# Fluid_Flow_FE.net
KiCad netlist of a schematic drawn in Altium Designer
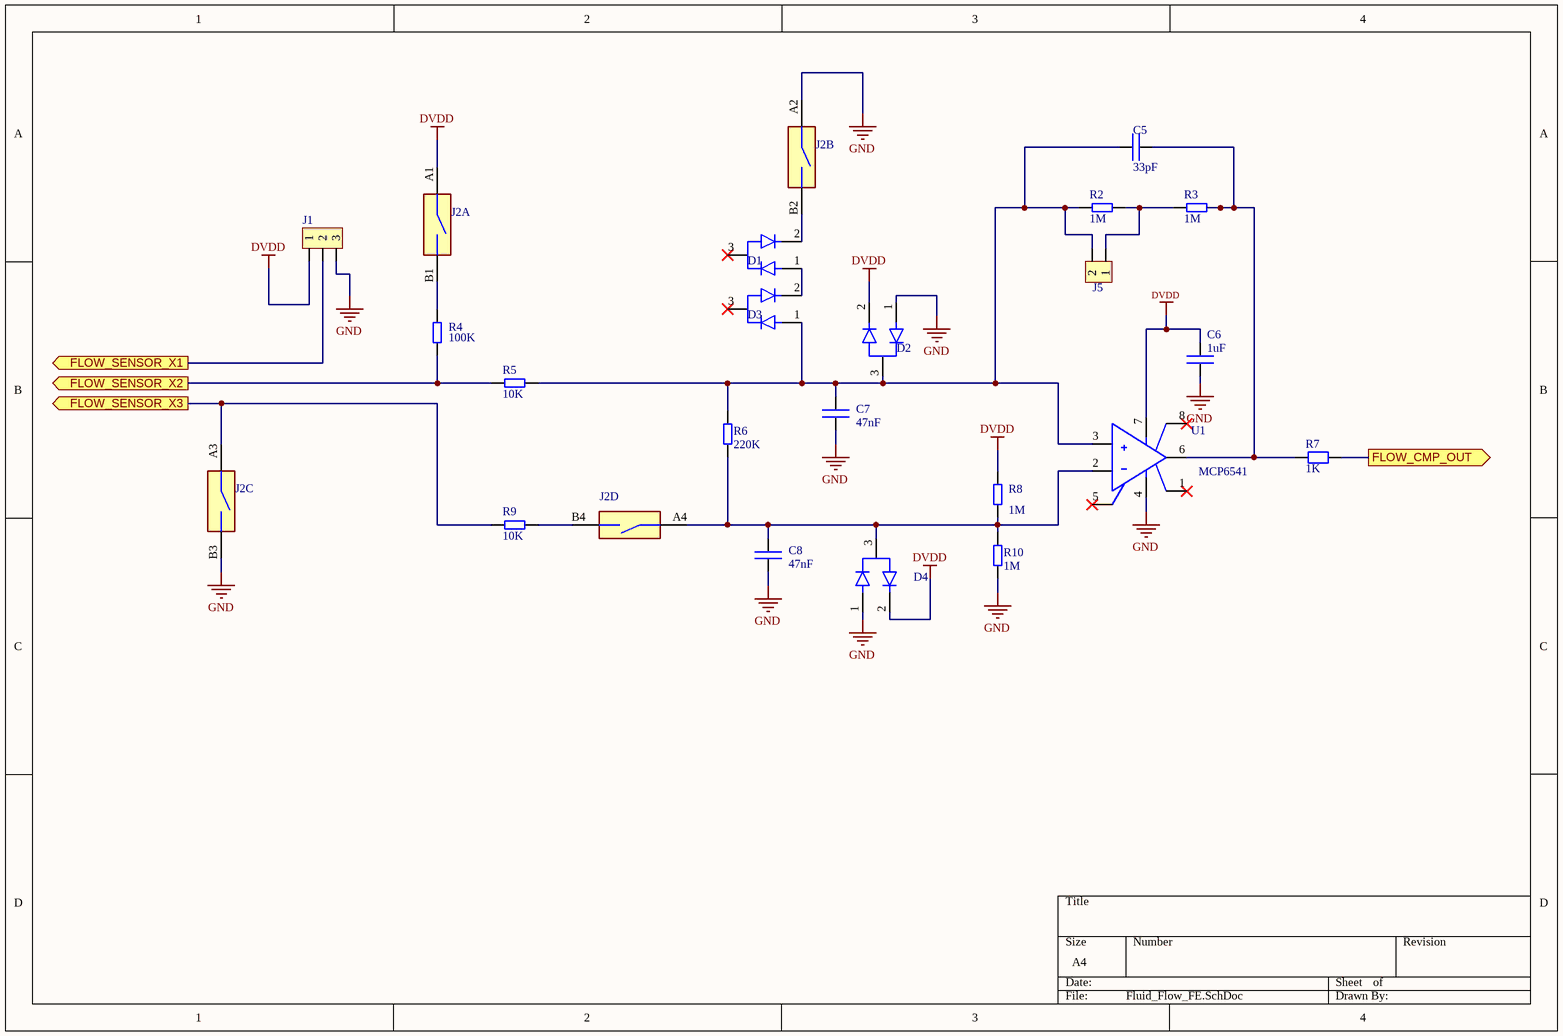
[diagram p0: Fluid_Flow_FE.SchDoc]

(export (version "E")
  (design (tool "Eeschema 10.0.6"))
  (components
    (comp (ref "C5")
      (value "33pF")
      (footprint "CAP_SM0603_YAGEOCC2_N")
      (description "CAP 33pF SM0603 NPO 50V YAGEO CC2")
      (fields
        (field (name "MANUFACTURER") "Yageo")
        (field (name "MANUFACTURER PART NUMBER") "CC0603JRNPO9BN330")
      )
      (libsource (lib "yageo") (part "CC0603JRNPO9BN330"))
    )
    (comp (ref "C6")
      (value "1uF")
      (footprint "CAP_SM0603_YAGEOCC2_N")
      (description "CAP 1uF SM0603 X7R 10V YAGEO CC2")
      (fields
        (field (name "MANUFACTURER") "Yageo")
        (field (name "MANUFACTURER PART NUMBER") "CC0603KRX7R6BB105")
      )
      (libsource (lib "yageo") (part "CC0603KRX7R6BB105"))
    )
    (comp (ref "C7")
      (value "47nF")
      (footprint "CAP_SM0603_YAGEOCC2_N")
      (description "CAP 47nF SM0603 X7R 16V YAGEO")
      (fields
        (field (name "MANUFACTURER") "Yageo")
        (field (name "MANUFACTURER PART NUMBER") "CC0603JRX7R7BB473")
      )
      (libsource (lib "yageo") (part "CC0603JRX7R7BB473"))
    )
    (comp (ref "C8")
      (value "47nF")
      (footprint "CAP_SM0603_YAGEOCC2_N")
      (description "CAP 47nF SM0603 X7R 16V YAGEO")
      (fields
        (field (name "MANUFACTURER") "Yageo")
        (field (name "MANUFACTURER PART NUMBER") "CC0603JRX7R7BB473")
      )
      (libsource (lib "yageo") (part "CC0603JRX7R7BB473"))
    )
    (comp (ref "D1")
      (value "BAV23S")
      (footprint "BAV23S")
      (description "DIODE ARRAY GP 250V 200MA SOT23")
      (fields (field (name "MANUFACTURER") "onsemi"))
      (libsource (lib "flowmeet") (part "BAV23S"))
    )
    (comp (ref "D2")
      (value "BAV23S")
      (footprint "BAV23S")
      (description "DIODE ARRAY GP 250V 200MA SOT23")
      (fields (field (name "MANUFACTURER") "onsemi"))
      (libsource (lib "flowmeet") (part "BAV23S"))
    )
    (comp (ref "D3")
      (value "BAV23S")
      (footprint "BAV23S")
      (description "DIODE ARRAY GP 250V 200MA SOT23")
      (fields (field (name "MANUFACTURER") "onsemi"))
      (libsource (lib "flowmeet") (part "BAV23S"))
    )
    (comp (ref "D4")
      (value "BAV23S")
      (footprint "BAV23S")
      (description "DIODE ARRAY GP 250V 200MA SOT23")
      (fields (field (name "MANUFACTURER") "onsemi"))
      (libsource (lib "flowmeet") (part "BAV23S"))
    )
    (comp (ref "J1")
      (value "54101-T0600LF-CUT-3")
      (footprint "HEADER PIN 1X3")
      (description "Pin header pitch 2.54 TH - cuttable 3 od 36 positions.")
      (fields
        (field (name "MANUFACTURER") "Amphenol ICC")
        (field (name "MANUFACTURER PART NUMBER") "54101-T0600LF")
      )
      (libsource (lib "flowmeet") (part "54101-T0600LF-CUT-3"))
    )
    (comp (ref "J2")
      (value "DSHP04TSGER_1")
      (footprint "DSHP04TSGER")
      (description "DIP Switches / SIP Switches 4pos 0.025A 24VDC 1/2 Pitch")
      (fields
        (field (name "MANUFACTURER") "Kangshen")
        (field (name "MANUFACTURER PART NUMBER") "DSHP04TSGER")
      )
      (libsource (lib "") (part "DSHP04TSGER_1_1"))
    )
    (comp (ref "J5")
      (value "54101-T0600LF-CUT-2")
      (footprint "HEADER PIN 1X2")
      (description "Pin header pitch 2.54 TH - cuttable 2 od 36 positions.")
      (fields
        (field (name "MANUFACTURER") "Amphenol ICC")
        (field (name "MANUFACTURER PART NUMBER") "54101-T0600LF")
      )
      (libsource (lib "flowmeet") (part "54101-T0600LF-CUT-2"))
    )
    (comp (ref "R2")
      (value "1M")
      (footprint "RES_SM0603_YAGEORC_N")
      (description "RES 1M SM0603 YAGEO RC_L")
      (fields
        (field (name "MANUFACTURER") "Yageo")
        (field (name "MANUFACTURER PART NUMBER") "RC0603FR-071ML")
      )
      (libsource (lib "") (part "RC0603FR-071ML_1"))
    )
    (comp (ref "R3")
      (value "1M")
      (footprint "RES_SM0603_YAGEORC_N")
      (description "RES 1M SM0603 YAGEO RC_L")
      (fields
        (field (name "MANUFACTURER") "Yageo")
        (field (name "MANUFACTURER PART NUMBER") "RC0603FR-071ML")
      )
      (libsource (lib "") (part "RC0603FR-071ML_1"))
    )
    (comp (ref "R4")
      (value "100K")
      (footprint "RES_SM0603_YAGEORC_N")
      (description "RES 100K SM0603 YAGEO RC_L")
      (fields
        (field (name "MANUFACTURER") "Yageo")
        (field (name "MANUFACTURER PART NUMBER") "RC0603FR-13100KL")
      )
      (libsource (lib "yageo") (part "RC0603FR-13100KL"))
    )
    (comp (ref "R5")
      (value "10K")
      (footprint "RES_SM0603_YAGEORC_N")
      (description "RES 10K SM0603 YAGEO RC_L")
      (fields
        (field (name "MANUFACTURER") "Yageo")
        (field (name "MANUFACTURER PART NUMBER") "RC0603FR-0710KL")
      )
      (libsource (lib "yageo") (part "RC0603FR-0710KL"))
    )
    (comp (ref "R6")
      (value "220K")
      (footprint "RES_SM0603_YAGEORC_N")
      (description "RES 220K SM0603 YAGEO RC_L")
      (fields
        (field (name "MANUFACTURER") "Yageo")
        (field (name "MANUFACTURER PART NUMBER") "RC0603FR-07220KL")
      )
      (libsource (lib "yageo") (part "RC0603FR-07220KL"))
    )
    (comp (ref "R7")
      (value "1K")
      (footprint "RES_SM0603_YAGEORC_N")
      (description "RES 1K SM0603 YAGEO RC_L")
      (fields
        (field (name "MANUFACTURER") "Yageo")
        (field (name "MANUFACTURER PART NUMBER") "RC0603FR-071KL")
      )
      (libsource (lib "yageo") (part "RC0603FR-071KL"))
    )
    (comp (ref "R8")
      (value "1M")
      (footprint "RES_SM0603_YAGEORC_N")
      (description "RES 1M SM0603 YAGEO RC_L")
      (fields
        (field (name "MANUFACTURER") "Yageo")
        (field (name "MANUFACTURER PART NUMBER") "RC0603FR-071ML")
      )
      (libsource (lib "yageo") (part "RC0603FR-071ML"))
    )
    (comp (ref "R9")
      (value "10K")
      (footprint "RES_SM0603_YAGEORC_N")
      (description "RES 10K SM0603 YAGEO RC_L")
      (fields
        (field (name "MANUFACTURER") "Yageo")
        (field (name "MANUFACTURER PART NUMBER") "RC0603FR-0710KL")
      )
      (libsource (lib "yageo") (part "RC0603FR-0710KL"))
    )
    (comp (ref "R10")
      (value "1M")
      (footprint "RES_SM0603_YAGEORC_N")
      (description "RES 1M SM0603 YAGEO RC_L")
      (fields
        (field (name "MANUFACTURER") "Yageo")
        (field (name "MANUFACTURER PART NUMBER") "RC0603FR-071ML")
      )
      (libsource (lib "yageo") (part "RC0603FR-071ML"))
    )
    (comp (ref "U1")
      (value "MCP6541")
      (footprint "MCP6541-E/SN")
      (description "IC COMP PP I/O SNGL 1.6V 8SOIC")
      (fields
        (field (name "MANUFACTURER") "Microchip Tech")
        (field (name "MANUFACTURER PART NUMBER") "MCP6541-E/SN")
      )
      (libsource (lib "flowmeet") (part "MCP6541-E/SN"))
    )
  )
  (nets
    (net (code "1") (name "/FLOW_CMP_OUT") (class "Default") (node (ref "R7") (pin "2") (pintype "passive")))
    (net (code "2") (name "/FLOW_SENSOR_X1") (class "Default")
      (node (ref "J1") (pin "2") (pinfunction "2_2") (pintype "passive"))
    )
    (net (code "3") (name "/FLOW_SENSOR_X2") (class "Default")
      (node (ref "R4") (pin "1") (pintype "passive"))
      (node (ref "R5") (pin "1") (pintype "passive"))
    )
    (net (code "4") (name "/FLOW_SENSOR_X3") (class "Default")
      (node (ref "J2") (pin "A3") (pinfunction "A3_A3") (pintype "passive"))
      (node (ref "R9") (pin "1") (pintype "passive"))
    )
    (net (code "5") (name "DVDD") (class "Default")
      (node (ref "C6") (pin "1") (pintype "passive"))
      (node (ref "D2") (pin "2") (pinfunction "2_2") (pintype "passive"))
      (node (ref "D4") (pin "2") (pinfunction "2_2") (pintype "passive"))
      (node (ref "J1") (pin "1") (pinfunction "1_1") (pintype "passive"))
      (node (ref "J2") (pin "A1") (pinfunction "A1_A1") (pintype "passive"))
      (node (ref "R8") (pin "2") (pintype "passive"))
      (node (ref "U1") (pin "7") (pinfunction "V+_7") (pintype "power_in"))
    )
    (net (code "6") (name "GND") (class "Default")
      (node (ref "C6") (pin "2") (pintype "passive"))
      (node (ref "C7") (pin "2") (pintype "passive"))
      (node (ref "C8") (pin "2") (pintype "passive"))
      (node (ref "D2") (pin "1") (pinfunction "1_1") (pintype "passive"))
      (node (ref "D4") (pin "1") (pinfunction "1_1") (pintype "passive"))
      (node (ref "J1") (pin "3") (pinfunction "3_3") (pintype "passive"))
      (node (ref "J2") (pin "A2") (pinfunction "A2_A2") (pintype "passive"))
      (node (ref "J2") (pin "B3") (pinfunction "B3_B3") (pintype "passive"))
      (node (ref "R10") (pin "1") (pintype "passive"))
      (node (ref "U1") (pin "4") (pinfunction "V-_4") (pintype "power_in"))
    )
    (net (code "7") (name "Net-(D1-Pad1)") (class "Default")
      (node (ref "D1") (pin "1") (pinfunction "1_1") (pintype "passive"))
      (node (ref "D3") (pin "2") (pinfunction "2_2") (pintype "passive"))
    )
    (net (code "8") (name "Net-(D1-Pad2)") (class "Default")
      (node (ref "D1") (pin "2") (pinfunction "2_2") (pintype "passive"))
      (node (ref "J2") (pin "B2") (pinfunction "B2_B2") (pintype "passive"))
    )
    (net (code "9") (name "Net-(J2-PadB1)") (class "Default")
      (node (ref "J2") (pin "B1") (pinfunction "B1_B1") (pintype "passive"))
      (node (ref "R4") (pin "2") (pintype "passive"))
    )
    (net (code "10") (name "Net-(J2-PadB4)") (class "Default")
      (node (ref "J2") (pin "B4") (pinfunction "B4_B4") (pintype "passive"))
      (node (ref "R9") (pin "2") (pintype "passive"))
    )
    (net (code "11") (name "Net-(J5-Pad1)") (class "Default")
      (node (ref "J5") (pin "1") (pinfunction "1_1") (pintype "passive"))
      (node (ref "R2") (pin "2") (pintype "passive"))
      (node (ref "R3") (pin "1") (pintype "passive"))
    )
    (net (code "12") (name "Net-(U1-IN+)") (class "Default")
      (node (ref "C5") (pin "1") (pintype "passive"))
      (node (ref "C7") (pin "1") (pintype "passive"))
      (node (ref "D2") (pin "3") (pinfunction "3_3") (pintype "passive"))
      (node (ref "D3") (pin "1") (pinfunction "1_1") (pintype "passive"))
      (node (ref "J5") (pin "2") (pinfunction "2_2") (pintype "passive"))
      (node (ref "R2") (pin "1") (pintype "passive"))
      (node (ref "R5") (pin "2") (pintype "passive"))
      (node (ref "R6") (pin "2") (pintype "passive"))
      (node (ref "U1") (pin "3") (pinfunction "IN+_3") (pintype "passive"))
    )
    (net (code "13") (name "Net-(U1-IN-)") (class "Default")
      (node (ref "C8") (pin "1") (pintype "passive"))
      (node (ref "D4") (pin "3") (pinfunction "3_3") (pintype "passive"))
      (node (ref "J2") (pin "A4") (pinfunction "A4_A4") (pintype "passive"))
      (node (ref "R10") (pin "2") (pintype "passive"))
      (node (ref "R6") (pin "1") (pintype "passive"))
      (node (ref "R8") (pin "1") (pintype "passive"))
      (node (ref "U1") (pin "2") (pinfunction "IN-_2") (pintype "passive"))
    )
    (net (code "14") (name "Net-(U1-OUT)") (class "Default")
      (node (ref "C5") (pin "2") (pintype "passive"))
      (node (ref "R3") (pin "2") (pintype "passive"))
      (node (ref "R7") (pin "1") (pintype "passive"))
      (node (ref "U1") (pin "6") (pinfunction "OUT_6") (pintype "passive"))
    )
    (net (code "15") (name "unconnected-(D1-Pad3)") (class "Default")
      (node (ref "D1") (pin "3") (pinfunction "3_3") (pintype "passive+no_connect"))
    )
    (net (code "16") (name "unconnected-(D3-Pad3)") (class "Default")
      (node (ref "D3") (pin "3") (pinfunction "3_3") (pintype "passive+no_connect"))
    )
    (net (code "17") (name "unconnected-(U1-OS_NUL-Pad1)") (class "Default")
      (node (ref "U1") (pin "1") (pinfunction "OS_NUL_1") (pintype "passive+no_connect"))
    )
    (net (code "18") (name "unconnected-(U1-OS_NUL-Pad5)") (class "Default")
      (node (ref "U1") (pin "5") (pinfunction "OS_NUL_5") (pintype "passive+no_connect"))
    )
    (net (code "19") (name "unconnected-(U1-TAB-Pad8)") (class "Default")
      (node (ref "U1") (pin "8") (pinfunction "TAB_8") (pintype "passive+no_connect"))
    )
  )
)
